# mssaPIC12smd.net
KiCad netlist of a schematic drawn in EAGLE
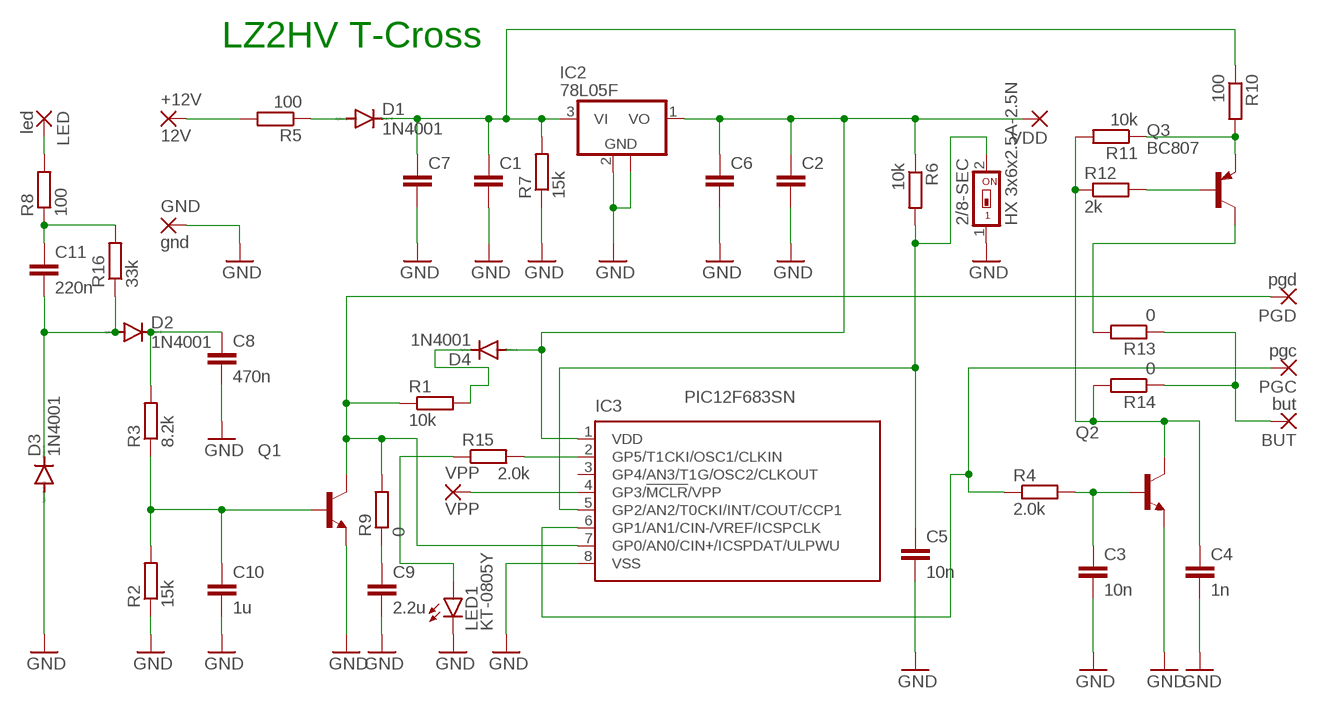
[diagram p0: schematic, sheet 1]

(export (version "E")
  (design (tool "Eeschema 10.0.6"))
  (components
    (comp (ref "+12V")
      (value "12V")
      (footprint "eagle-import:3,17_1,3")
      (libsource (lib "eagle-import") (part "3,17/1,3"))
    )
    (comp (ref "2/8-SEC")
      (value "HX 3x6x2.5A-2.5N")
      (footprint "eagle-import:SMS-001")
      (libsource (lib "eagle-import") (part "SWS001"))
    )
    (comp (ref "BUT")
      (value "but")
      (footprint "eagle-import:3,17_1,3")
      (libsource (lib "eagle-import") (part "3,17/1,3"))
    )
    (comp (ref "C1")
      (value "100n")
      (footprint "eagle-import:C1206K")
      (libsource (lib "eagle-import") (part "C-EUC1206K"))
    )
    (comp (ref "C2")
      (value "220n")
      (footprint "eagle-import:C1206K")
      (libsource (lib "eagle-import") (part "C-EUC1206K"))
    )
    (comp (ref "C3")
      (value "10n")
      (footprint "eagle-import:C1206K")
      (libsource (lib "eagle-import") (part "C-EUC1206K"))
    )
    (comp (ref "C4")
      (value "1n")
      (footprint "eagle-import:C1206K")
      (libsource (lib "eagle-import") (part "C-EUC1206K"))
    )
    (comp (ref "C5")
      (value "10n")
      (footprint "eagle-import:C1206K")
      (libsource (lib "eagle-import") (part "C-EUC1206K"))
    )
    (comp (ref "C6")
      (value "100n")
      (footprint "eagle-import:C1206K")
      (libsource (lib "eagle-import") (part "C-EUC1206K"))
    )
    (comp (ref "C7")
      (value "100n")
      (footprint "eagle-import:C1206K")
      (libsource (lib "eagle-import") (part "C-EUC1206K"))
    )
    (comp (ref "C8")
      (value "470n")
      (footprint "eagle-import:C1206K")
      (libsource (lib "eagle-import") (part "C-EUC1206K"))
    )
    (comp (ref "C9")
      (value "2.2u")
      (footprint "eagle-import:C1206K")
      (libsource (lib "eagle-import") (part "C-EUC1206K"))
    )
    (comp (ref "C10")
      (value "1u")
      (footprint "eagle-import:C1206K")
      (libsource (lib "eagle-import") (part "C-EUC1206K"))
    )
    (comp (ref "C11")
      (value "220n")
      (footprint "eagle-import:C1206K")
      (libsource (lib "eagle-import") (part "C-EUC1206K"))
    )
    (comp (ref "D1")
      (value "1N4001")
      (footprint "eagle-import:SOD-123_MINI-SMA")
      (libsource (lib "eagle-import") (part "CGRM400-G1"))
    )
    (comp (ref "D2")
      (value "1N4001")
      (footprint "eagle-import:SOD-123_MINI-SMA")
      (libsource (lib "eagle-import") (part "CGRM400-G1"))
    )
    (comp (ref "D3")
      (value "1N4001")
      (footprint "eagle-import:SOD-123_MINI-SMA")
      (libsource (lib "eagle-import") (part "CGRM400-G1"))
    )
    (comp (ref "D4")
      (value "1N4001")
      (footprint "eagle-import:SOD-123_MINI-SMA")
      (libsource (lib "eagle-import") (part "CGRM400-G1"))
    )
    (comp (ref "GND")
      (value "gnd")
      (footprint "eagle-import:3,17_1,3")
      (libsource (lib "eagle-import") (part "3,17/1,3"))
    )
    (comp (ref "IC2")
      (value "78L05F")
      (footprint "eagle-import:SOT89")
      (libsource (lib "eagle-import") (part "78LF05"))
    )
    (comp (ref "IC3")
      (value "PIC12F683SN")
      (footprint "eagle-import:SO-08")
      (fields (field (name "MF") "MICROCHIP") (field (name "MPN") "PIC12F683-I/SN"))
      (libsource (lib "eagle-import") (part "PIC12F683SN"))
    )
    (comp (ref "LED")
      (value "led")
      (footprint "eagle-import:3,17_1,3")
      (libsource (lib "eagle-import") (part "3,17/1,3"))
    )
    (comp (ref "LED1")
      (value "KT-0805Y")
      (footprint "eagle-import:CHIP-LED0805")
      (libsource (lib "eagle-import") (part "LEDCHIP-LED0805"))
    )
    (comp (ref "PGC")
      (value "pgc")
      (footprint "eagle-import:2,15_1,0")
      (libsource (lib "eagle-import") (part "2,15/1,0"))
    )
    (comp (ref "PGD")
      (value "pgd")
      (footprint "eagle-import:2,15_1,0")
      (libsource (lib "eagle-import") (part "2,15/1,0"))
    )
    (comp (ref "Q1")
      (value "BC817")
      (footprint "eagle-import:SOT23-BEC")
      (libsource (lib "eagle-import") (part "BC817SMD-40LT1"))
    )
    (comp (ref "Q2")
      (value "BC817")
      (footprint "eagle-import:SOT23-BEC")
      (libsource (lib "eagle-import") (part "BC817SMD-40LT1"))
    )
    (comp (ref "Q3")
      (value "BC807")
      (footprint "eagle-import:SOT23-BEC")
      (libsource (lib "eagle-import") (part "BC807SMD-40"))
    )
    (comp (ref "R1")
      (value "10k")
      (footprint "eagle-import:M1206")
      (libsource (lib "eagle-import") (part "R-EU_M1206"))
    )
    (comp (ref "R2")
      (value "15k")
      (footprint "eagle-import:M1206")
      (libsource (lib "eagle-import") (part "R-EU_M1206"))
    )
    (comp (ref "R3")
      (value "8.2k")
      (footprint "eagle-import:M1206")
      (libsource (lib "eagle-import") (part "R-EU_M1206"))
    )
    (comp (ref "R4")
      (value "2.0k")
      (footprint "eagle-import:M1206")
      (libsource (lib "eagle-import") (part "R-EU_M1206"))
    )
    (comp (ref "R5")
      (value "100")
      (footprint "eagle-import:M1206")
      (libsource (lib "eagle-import") (part "R-EU_M1206"))
    )
    (comp (ref "R6")
      (value "10k")
      (footprint "eagle-import:M1206")
      (libsource (lib "eagle-import") (part "R-EU_M1206"))
    )
    (comp (ref "R7")
      (value "15k")
      (footprint "eagle-import:M1206")
      (libsource (lib "eagle-import") (part "R-EU_M1206"))
    )
    (comp (ref "R8")
      (value "100")
      (footprint "eagle-import:M1206")
      (libsource (lib "eagle-import") (part "R-EU_M1206"))
    )
    (comp (ref "R9")
      (value "0")
      (footprint "eagle-import:R0603")
      (libsource (lib "eagle-import") (part "R-EU_R0603"))
    )
    (comp (ref "R10")
      (value "100")
      (footprint "eagle-import:M1206")
      (libsource (lib "eagle-import") (part "R-EU_M1206"))
    )
    (comp (ref "R11")
      (value "10k")
      (footprint "eagle-import:M1206")
      (libsource (lib "eagle-import") (part "R-EU_M1206"))
    )
    (comp (ref "R12")
      (value "2k")
      (footprint "eagle-import:M1206")
      (libsource (lib "eagle-import") (part "R-EU_M1206"))
    )
    (comp (ref "R13")
      (value "0")
      (footprint "eagle-import:R0603")
      (libsource (lib "eagle-import") (part "R-EU_R0603"))
    )
    (comp (ref "R14")
      (value "0")
      (footprint "eagle-import:R0603")
      (libsource (lib "eagle-import") (part "R-EU_R0603"))
    )
    (comp (ref "R15")
      (value "2.0k")
      (footprint "eagle-import:R0603")
      (libsource (lib "eagle-import") (part "R-EU_R0603"))
    )
    (comp (ref "R16")
      (value "33k")
      (footprint "eagle-import:M1206")
      (libsource (lib "eagle-import") (part "R-EU_M1206"))
    )
    (comp (ref "VDD")
      (value "VDD")
      (footprint "eagle-import:2,15_1,0")
      (libsource (lib "eagle-import") (part "2,15/1,0"))
    )
    (comp (ref "VPP")
      (value "VPP")
      (footprint "eagle-import:2,15_1,0")
      (libsource (lib "eagle-import") (part "2,15/1,0"))
    )
  )
  (nets
    (net (code "1") (name "GND") (class "Default")
      (node (ref "2/8-SEC") (pin "1") (pinfunction "1_1") (pintype "passive"))
      (node (ref "C1") (pin "2") (pinfunction "2_2") (pintype "passive"))
      (node (ref "C10") (pin "2") (pinfunction "2_2") (pintype "passive"))
      (node (ref "C2") (pin "2") (pinfunction "2_2") (pintype "passive"))
      (node (ref "C3") (pin "2") (pinfunction "2_2") (pintype "passive"))
      (node (ref "C4") (pin "2") (pinfunction "2_2") (pintype "passive"))
      (node (ref "C5") (pin "2") (pinfunction "2_2") (pintype "passive"))
      (node (ref "C6") (pin "2") (pinfunction "2_2") (pintype "passive"))
      (node (ref "C7") (pin "2") (pinfunction "2_2") (pintype "passive"))
      (node (ref "C8") (pin "2") (pinfunction "2_2") (pintype "passive"))
      (node (ref "C9") (pin "2") (pinfunction "2_2") (pintype "passive"))
      (node (ref "D3") (pin "A") (pinfunction "A_A") (pintype "passive"))
      (node (ref "GND") (pin "1") (pinfunction "P_1") (pintype "passive"))
      (node (ref "IC2") (pin "2") (pinfunction "GND_2") (pintype "passive"))
      (node (ref "IC2") (pin "2@1") (pinfunction "GND_2@1") (pintype "passive"))
      (node (ref "IC3") (pin "8") (pinfunction "VSS_8") (pintype "power_in"))
      (node (ref "LED1") (pin "C") (pinfunction "C_C") (pintype "passive"))
      (node (ref "Q1") (pin "E") (pinfunction "E_E") (pintype "passive"))
      (node (ref "Q2") (pin "E") (pinfunction "E_E") (pintype "passive"))
      (node (ref "R2") (pin "1") (pinfunction "1_1") (pintype "passive"))
      (node (ref "R7") (pin "1") (pinfunction "1_1") (pintype "passive"))
    )
    (net (code "2") (name "Net-(+12V-P)") (class "Default")
      (node (ref "+12V") (pin "1") (pinfunction "P_1") (pintype "passive"))
      (node (ref "R5") (pin "2") (pinfunction "2_2") (pintype "passive"))
    )
    (net (code "3") (name "Net-(BUT-P)") (class "Default")
      (node (ref "BUT") (pin "1") (pinfunction "P_1") (pintype "passive"))
      (node (ref "R13") (pin "1") (pinfunction "1_1") (pintype "passive"))
      (node (ref "R14") (pin "1") (pinfunction "1_1") (pintype "passive"))
    )
    (net (code "4") (name "Net-(C3-Pad1)") (class "Default")
      (node (ref "C3") (pin "1") (pinfunction "1_1") (pintype "passive"))
      (node (ref "Q2") (pin "B") (pinfunction "B_B") (pintype "passive"))
      (node (ref "R4") (pin "2") (pinfunction "2_2") (pintype "passive"))
    )
    (net (code "5") (name "Net-(C4-Pad1)") (class "Default")
      (node (ref "C4") (pin "1") (pinfunction "1_1") (pintype "passive"))
      (node (ref "Q2") (pin "C") (pinfunction "C_C") (pintype "passive"))
      (node (ref "R11") (pin "2") (pinfunction "2_2") (pintype "passive"))
      (node (ref "R12") (pin "1") (pinfunction "1_1") (pintype "passive"))
      (node (ref "R14") (pin "2") (pinfunction "2_2") (pintype "passive"))
    )
    (net (code "6") (name "Net-(C8-Pad1)") (class "Default")
      (node (ref "C8") (pin "1") (pinfunction "1_1") (pintype "passive"))
      (node (ref "D2") (pin "C") (pinfunction "C_C") (pintype "passive"))
      (node (ref "R3") (pin "2") (pinfunction "2_2") (pintype "passive"))
    )
    (net (code "7") (name "Net-(C9-Pad1)") (class "Default")
      (node (ref "C9") (pin "1") (pinfunction "1_1") (pintype "passive"))
      (node (ref "R9") (pin "1") (pinfunction "1_1") (pintype "passive"))
    )
    (net (code "8") (name "Net-(C10-Pad1)") (class "Default")
      (node (ref "C10") (pin "1") (pinfunction "1_1") (pintype "passive"))
      (node (ref "Q1") (pin "B") (pinfunction "B_B") (pintype "passive"))
      (node (ref "R2") (pin "2") (pinfunction "2_2") (pintype "passive"))
      (node (ref "R3") (pin "1") (pinfunction "1_1") (pintype "passive"))
    )
    (net (code "9") (name "Net-(C11-Pad1)") (class "Default")
      (node (ref "C11") (pin "1") (pinfunction "1_1") (pintype "passive"))
      (node (ref "R16") (pin "2") (pinfunction "2_2") (pintype "passive"))
      (node (ref "R8") (pin "1") (pinfunction "1_1") (pintype "passive"))
    )
    (net (code "10") (name "Net-(C11-Pad2)") (class "Default")
      (node (ref "C11") (pin "2") (pinfunction "2_2") (pintype "passive"))
      (node (ref "D2") (pin "A") (pinfunction "A_A") (pintype "passive"))
      (node (ref "D3") (pin "C") (pinfunction "C_C") (pintype "passive"))
      (node (ref "R16") (pin "1") (pinfunction "1_1") (pintype "passive"))
    )
    (net (code "11") (name "Net-(D1-PadA)") (class "Default")
      (node (ref "D1") (pin "A") (pinfunction "A_A") (pintype "passive"))
      (node (ref "R5") (pin "1") (pinfunction "1_1") (pintype "passive"))
    )
    (net (code "12") (name "Net-(D4-PadC)") (class "Default")
      (node (ref "D4") (pin "C") (pinfunction "C_C") (pintype "passive"))
      (node (ref "R1") (pin "2") (pinfunction "2_2") (pintype "passive"))
    )
    (net (code "13") (name "Net-(IC2-VI)") (class "Default")
      (node (ref "C1") (pin "1") (pinfunction "1_1") (pintype "passive"))
      (node (ref "C7") (pin "1") (pinfunction "1_1") (pintype "passive"))
      (node (ref "D1") (pin "C") (pinfunction "C_C") (pintype "passive"))
      (node (ref "IC2") (pin "3") (pinfunction "VI_3") (pintype "input"))
      (node (ref "R10") (pin "1") (pinfunction "1_1") (pintype "passive"))
      (node (ref "R7") (pin "2") (pinfunction "2_2") (pintype "passive"))
    )
    (net (code "14") (name "Net-(IC2-VO)") (class "Default")
      (node (ref "C2") (pin "1") (pinfunction "1_1") (pintype "passive"))
      (node (ref "C6") (pin "1") (pinfunction "1_1") (pintype "passive"))
      (node (ref "D4") (pin "A") (pinfunction "A_A") (pintype "passive"))
      (node (ref "IC2") (pin "1") (pinfunction "VO_1") (pintype "passive"))
      (node (ref "IC3") (pin "1") (pinfunction "VDD_1") (pintype "power_in"))
      (node (ref "R6") (pin "1") (pinfunction "1_1") (pintype "passive"))
      (node (ref "VDD") (pin "1") (pinfunction "P_1") (pintype "passive"))
    )
    (net (code "15") (name "Net-(IC3-GP0{slash}AN0{slash}CIN+{slash}ICSPDAT{slash}ULPWU)") (class "Default")
      (node (ref "IC3") (pin "7") (pinfunction "GP0/AN0/CIN+/ICSPDAT/ULPWU_7") (pintype "bidirectional"))
      (node (ref "PGD") (pin "1") (pinfunction "P_1") (pintype "passive"))
      (node (ref "Q1") (pin "C") (pinfunction "C_C") (pintype "passive"))
      (node (ref "R1") (pin "1") (pinfunction "1_1") (pintype "passive"))
      (node (ref "R9") (pin "2") (pinfunction "2_2") (pintype "passive"))
    )
    (net (code "16") (name "Net-(IC3-GP1{slash}AN1{slash}CIN-{slash}VREF{slash}ICSPCLK)") (class "Default")
      (node (ref "IC3") (pin "6") (pinfunction "GP1/AN1/CIN-/VREF/ICSPCLK_6") (pintype "bidirectional"))
      (node (ref "PGC") (pin "1") (pinfunction "P_1") (pintype "passive"))
      (node (ref "R4") (pin "1") (pinfunction "1_1") (pintype "passive"))
    )
    (net (code "17") (name "Net-(IC3-GP2{slash}AN2{slash}T0CKI{slash}INT{slash}COUT{slash}CCP1)") (class "Default")
      (node (ref "2/8-SEC") (pin "2") (pinfunction "2_2") (pintype "passive"))
      (node (ref "C5") (pin "1") (pinfunction "1_1") (pintype "passive"))
      (node (ref "IC3") (pin "5") (pinfunction "GP2/AN2/T0CKI/INT/COUT/CCP1_5") (pintype "bidirectional"))
      (node (ref "R6") (pin "2") (pinfunction "2_2") (pintype "passive"))
    )
    (net (code "18") (name "Net-(IC3-GP3{slash}~{MCLR}{slash}VPP)") (class "Default")
      (node (ref "IC3") (pin "4") (pinfunction "GP3/~{MCLR}/VPP_4") (pintype "bidirectional"))
      (node (ref "VPP") (pin "1") (pinfunction "P_1") (pintype "passive"))
    )
    (net (code "19") (name "Net-(IC3-GP5{slash}T1CKI{slash}OSC1{slash}CLKIN)") (class "Default")
      (node (ref "IC3") (pin "2") (pinfunction "GP5/T1CKI/OSC1/CLKIN_2") (pintype "bidirectional"))
      (node (ref "R15") (pin "2") (pinfunction "2_2") (pintype "passive"))
    )
    (net (code "20") (name "Net-(LED-P)") (class "Default")
      (node (ref "LED") (pin "1") (pinfunction "P_1") (pintype "passive"))
      (node (ref "R8") (pin "2") (pinfunction "2_2") (pintype "passive"))
    )
    (net (code "21") (name "Net-(LED1-PadA)") (class "Default")
      (node (ref "LED1") (pin "A") (pinfunction "A_A") (pintype "passive"))
      (node (ref "R15") (pin "1") (pinfunction "1_1") (pintype "passive"))
    )
    (net (code "22") (name "Net-(Q3-PadB)") (class "Default")
      (node (ref "Q3") (pin "B") (pinfunction "B_B") (pintype "passive"))
      (node (ref "R12") (pin "2") (pinfunction "2_2") (pintype "passive"))
    )
    (net (code "23") (name "Net-(Q3-PadC)") (class "Default")
      (node (ref "Q3") (pin "C") (pinfunction "C_C") (pintype "passive"))
      (node (ref "R13") (pin "2") (pinfunction "2_2") (pintype "passive"))
    )
    (net (code "24") (name "Net-(Q3-PadE)") (class "Default")
      (node (ref "Q3") (pin "E") (pinfunction "E_E") (pintype "passive"))
      (node (ref "R10") (pin "2") (pinfunction "2_2") (pintype "passive"))
      (node (ref "R11") (pin "1") (pinfunction "1_1") (pintype "passive"))
    )
    (net (code "25") (name "unconnected-(IC3-GP4{slash}AN3{slash}T1G{slash}OSC2{slash}CLKOUT-Pad3)") (class "Default")
      (node (ref "IC3") (pin "3") (pinfunction "GP4/AN3/T1G/OSC2/CLKOUT_3") (pintype "bidirectional"))
    )
  )
)
